# USB_UART_C.net
KiCad netlist of a schematic drawn in Altium Designer
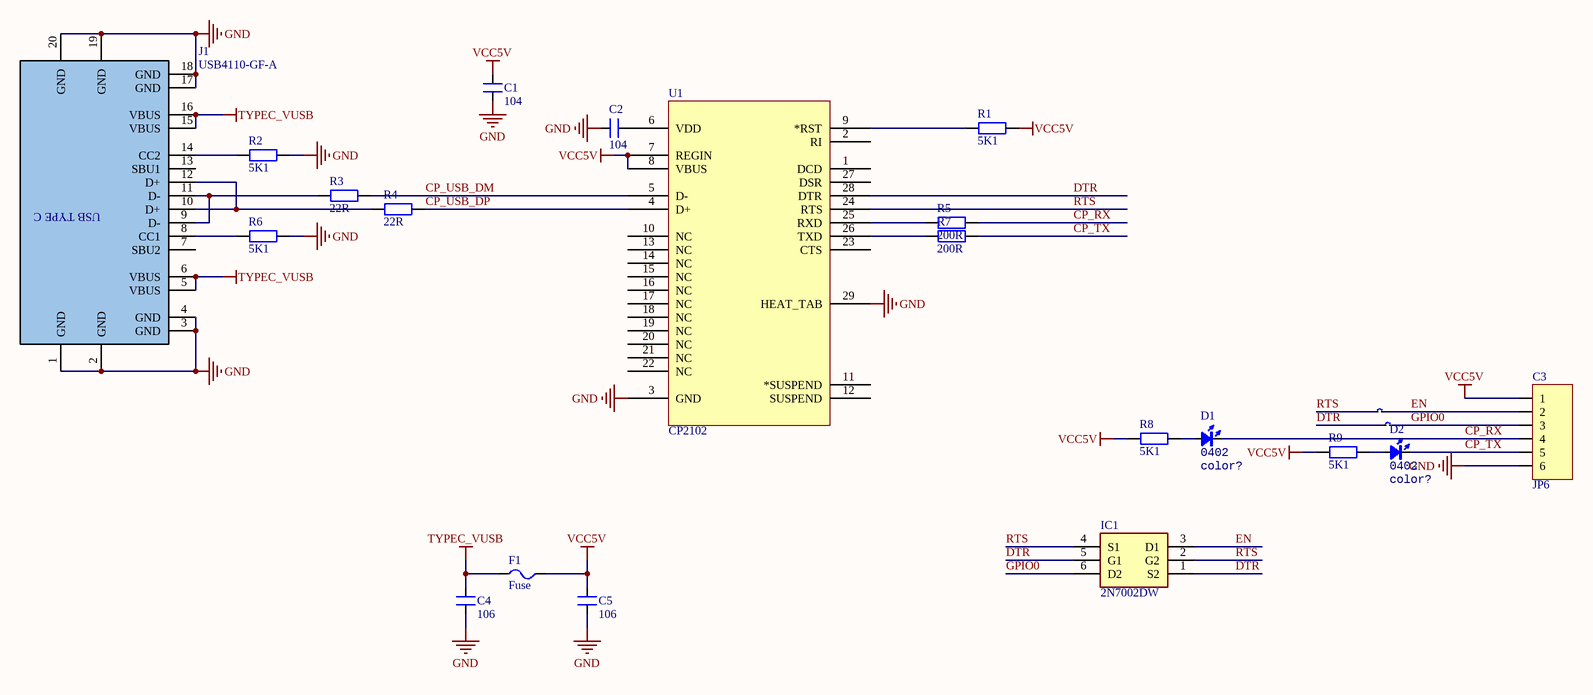
[diagram p0: USB_UART_C.SchDoc]

(export (version "E")
  (design (tool "Eeschema 10.0.6"))
  (components
    (comp (ref "C1")
      (value "104")
      (footprint "CAP_0402")
      (description "Cap SMD")
      (libsource (lib "OBIT_TESLA") (part "CM"))
    )
    (comp (ref "C2")
      (value "104")
      (footprint "CAP_0402")
      (description "Cap SMD")
      (libsource (lib "OBIT_TESLA") (part "CM"))
    )
    (comp (ref "C3")
      (value "JP6")
      (footprint "JP6-C1T")
      (description "WR-PHD 2.54 mm Angled Socket Header")
      (fields
        (field (name "MANUFACTURER") "Würth Elektronik eiSos GmbH")
        (field (name "PARTNO") "613006143121")
        (field (name "CREATED BY") "Karrer Zheng")
      )
      (libsource (lib "OBIT_TESLA") (part "JP6"))
    )
    (comp (ref "C4")
      (value "106")
      (footprint "CAP_0402")
      (description "Cap SMD")
      (libsource (lib "OBIT_TESLA") (part "CM"))
    )
    (comp (ref "C5")
      (value "106")
      (footprint "CAP_0402")
      (description "Cap SMD")
      (libsource (lib "OBIT_TESLA") (part "CM"))
    )
    (comp (ref "D1")
      (value "color?")
      (footprint "LED_0402_RED")
      (description "LED")
      (fields (field (name "TYPE") "0402"))
      (libsource (lib "OBIT_TESLA") (part "LED_0402"))
    )
    (comp (ref "D2")
      (value "color?")
      (footprint "LED_0402_RED")
      (description "LED")
      (fields (field (name "TYPE") "0402"))
      (libsource (lib "OBIT_TESLA") (part "LED_0402"))
    )
    (comp (ref "F1") (value "Fuse") (footprint "RES-SMD-1812") (libsource (lib "OBIT_TESLA") (part "FUSE")))
    (comp (ref "IC1")
      (value "2N7002DW")
      (footprint "SOT65P210X110-6N")
      (description "Integrated Circuit")
      (fields (field (name "MOUSER PART NUMBER") "512-2N7002DW"))
      (libsource (lib "OBIT_TESLA") (part "2N7002DW"))
    )
    (comp (ref "J1")
      (value "USB4110-GF-A")
      (footprint "USB4110GFA")
      (description "USB TYPE C")
      (libsource (lib "OBIT_TESLA") (part "USB4110-GF-A"))
    )
    (comp (ref "R1")
      (value "5K1")
      (footprint "RES_0402")
      (description "Resistor R1/4W")
      (libsource (lib "OBIT_TESLA") (part "R"))
    )
    (comp (ref "R2")
      (value "5K1")
      (footprint "RES_0402")
      (description "Resistor R1/4W")
      (libsource (lib "OBIT_TESLA") (part "R"))
    )
    (comp (ref "R3")
      (value "22R")
      (footprint "RES_0402")
      (description "Resistor R1/4W")
      (libsource (lib "OBIT_TESLA") (part "R"))
    )
    (comp (ref "R4")
      (value "22R")
      (footprint "RES_0402")
      (description "Resistor R1/4W")
      (libsource (lib "OBIT_TESLA") (part "R"))
    )
    (comp (ref "R5")
      (value "200R")
      (footprint "RES_0402")
      (description "Resistor R1/4W")
      (libsource (lib "OBIT_TESLA") (part "R"))
    )
    (comp (ref "R6")
      (value "5K1")
      (footprint "RES_0402")
      (description "Resistor R1/4W")
      (libsource (lib "OBIT_TESLA") (part "R"))
    )
    (comp (ref "R7")
      (value "200R")
      (footprint "RES_0402")
      (description "Resistor R1/4W")
      (libsource (lib "OBIT_TESLA") (part "R"))
    )
    (comp (ref "R8")
      (value "5K1")
      (footprint "RES_0402")
      (description "Resistor R1/4W")
      (libsource (lib "OBIT_TESLA") (part "R"))
    )
    (comp (ref "R9")
      (value "5K1")
      (footprint "RES_0402")
      (description "Resistor R1/4W")
      (libsource (lib "OBIT_TESLA") (part "R"))
    )
    (comp (ref "SB1") (value "SB") (footprint "SB_0603") (libsource (lib "OBIT_TESLA") (part "SB")))
    (comp (ref "SB2") (value "SB") (footprint "SB_0603") (libsource (lib "OBIT_TESLA") (part "SB")))
    (comp (ref "U1")
      (value "CP2102")
      (footprint "QFN-28")
      (description "USB to TTL")
      (libsource (lib "OBIT_TESLA") (part "CP2102"))
    )
  )
  (nets
    (net (code "1") (name "/CP_RX") (class "Default")
      (node (ref "C3") (pin "4") (pinfunction "4_4") (pintype "passive"))
      (node (ref "D1") (pin "2") (pinfunction "K_2") (pintype "passive"))
      (node (ref "R5") (pin "2") (pinfunction "2_2") (pintype "passive"))
    )
    (net (code "2") (name "/CP_TX") (class "Default")
      (node (ref "C3") (pin "5") (pinfunction "5_5") (pintype "passive"))
      (node (ref "D2") (pin "2") (pinfunction "K_2") (pintype "passive"))
      (node (ref "R7") (pin "2") (pinfunction "2_2") (pintype "passive"))
    )
    (net (code "3") (name "/CP_USB_DM") (class "Default")
      (node (ref "R3") (pin "2") (pinfunction "2_2") (pintype "passive"))
      (node (ref "U1") (pin "5") (pinfunction "D-_5") (pintype "passive"))
    )
    (net (code "4") (name "/CP_USB_DP") (class "Default")
      (node (ref "R4") (pin "2") (pinfunction "2_2") (pintype "passive"))
      (node (ref "U1") (pin "4") (pinfunction "D+_4") (pintype "passive"))
    )
    (net (code "5") (name "/DTR") (class "Default")
      (node (ref "IC1") (pin "1") (pinfunction "S2_1") (pintype "passive"))
      (node (ref "IC1") (pin "5") (pinfunction "G1_5") (pintype "passive"))
      (node (ref "SB2") (pin "1") (pintype "passive"))
      (node (ref "U1") (pin "28") (pinfunction "DTR_28") (pintype "passive"))
    )
    (net (code "6") (name "/EN") (class "Default")
      (node (ref "C3") (pin "2") (pinfunction "2_2") (pintype "passive"))
      (node (ref "IC1") (pin "3") (pinfunction "D1_3") (pintype "passive"))
      (node (ref "SB1") (pin "2") (pintype "passive"))
    )
    (net (code "7") (name "/GPIO0") (class "Default")
      (node (ref "C3") (pin "3") (pinfunction "3_3") (pintype "passive"))
      (node (ref "IC1") (pin "6") (pinfunction "D2_6") (pintype "passive"))
      (node (ref "SB2") (pin "2") (pintype "passive"))
    )
    (net (code "8") (name "/RTS") (class "Default")
      (node (ref "IC1") (pin "2") (pinfunction "G2_2") (pintype "passive"))
      (node (ref "IC1") (pin "4") (pinfunction "S1_4") (pintype "passive"))
      (node (ref "SB1") (pin "1") (pintype "passive"))
      (node (ref "U1") (pin "24") (pinfunction "RTS_24") (pintype "passive"))
    )
    (net (code "9") (name "GND") (class "Default")
      (node (ref "C1") (pin "2") (pinfunction "2_2") (pintype "passive"))
      (node (ref "C2") (pin "1") (pinfunction "1_1") (pintype "passive"))
      (node (ref "C3") (pin "6") (pinfunction "6_6") (pintype "passive"))
      (node (ref "C4") (pin "2") (pinfunction "2_2") (pintype "passive"))
      (node (ref "C5") (pin "2") (pinfunction "2_2") (pintype "passive"))
      (node (ref "J1") (pin "1") (pinfunction "GND_1") (pintype "passive"))
      (node (ref "J1") (pin "17") (pinfunction "GND_17") (pintype "passive"))
      (node (ref "J1") (pin "18") (pinfunction "GND_18") (pintype "passive"))
      (node (ref "J1") (pin "19") (pinfunction "GND_19") (pintype "passive"))
      (node (ref "J1") (pin "2") (pinfunction "GND_2") (pintype "passive"))
      (node (ref "J1") (pin "20") (pinfunction "GND_20") (pintype "passive"))
      (node (ref "J1") (pin "3") (pinfunction "GND_3") (pintype "passive"))
      (node (ref "J1") (pin "4") (pinfunction "GND_4") (pintype "passive"))
      (node (ref "R2") (pin "2") (pinfunction "2_2") (pintype "passive"))
      (node (ref "R6") (pin "2") (pinfunction "2_2") (pintype "passive"))
      (node (ref "U1") (pin "29") (pinfunction "HEAT_TAB_29") (pintype "passive"))
      (node (ref "U1") (pin "3") (pinfunction "GND_3") (pintype "passive"))
    )
    (net (code "10") (name "Net-(D1-A)") (class "Default")
      (node (ref "D1") (pin "1") (pinfunction "A_1") (pintype "passive"))
      (node (ref "R8") (pin "1") (pinfunction "1_1") (pintype "passive"))
    )
    (net (code "11") (name "Net-(D2-A)") (class "Default")
      (node (ref "D2") (pin "1") (pinfunction "A_1") (pintype "passive"))
      (node (ref "R9") (pin "1") (pinfunction "1_1") (pintype "passive"))
    )
    (net (code "12") (name "Net-(J1-CC1)") (class "Default")
      (node (ref "J1") (pin "8") (pinfunction "CC1_8") (pintype "passive"))
      (node (ref "R6") (pin "1") (pinfunction "1_1") (pintype "passive"))
    )
    (net (code "13") (name "Net-(J1-CC2)") (class "Default")
      (node (ref "J1") (pin "14") (pinfunction "CC2_14") (pintype "passive"))
      (node (ref "R2") (pin "1") (pinfunction "1_1") (pintype "passive"))
    )
    (net (code "14") (name "Net-(J1-D+-Pad10)") (class "Default")
      (node (ref "J1") (pin "10") (pinfunction "D+_10") (pintype "passive"))
      (node (ref "J1") (pin "12") (pinfunction "D+_12") (pintype "passive"))
      (node (ref "R4") (pin "1") (pinfunction "1_1") (pintype "passive"))
    )
    (net (code "15") (name "Net-(J1-D--Pad11)") (class "Default")
      (node (ref "J1") (pin "11") (pinfunction "D-_11") (pintype "passive"))
      (node (ref "J1") (pin "9") (pinfunction "D-_9") (pintype "passive"))
      (node (ref "R3") (pin "1") (pinfunction "1_1") (pintype "passive"))
    )
    (net (code "16") (name "Net-(U1-*RST)") (class "Default")
      (node (ref "R1") (pin "1") (pinfunction "1_1") (pintype "passive"))
      (node (ref "U1") (pin "9") (pinfunction "*RST_9") (pintype "passive"))
    )
    (net (code "17") (name "Net-(U1-RXD)") (class "Default")
      (node (ref "R5") (pin "1") (pinfunction "1_1") (pintype "passive"))
      (node (ref "U1") (pin "25") (pinfunction "RXD_25") (pintype "passive"))
    )
    (net (code "18") (name "Net-(U1-TXD)") (class "Default")
      (node (ref "R7") (pin "1") (pinfunction "1_1") (pintype "passive"))
      (node (ref "U1") (pin "26") (pinfunction "TXD_26") (pintype "passive"))
    )
    (net (code "19") (name "Net-(U1-VDD)") (class "Default")
      (node (ref "C2") (pin "2") (pinfunction "2_2") (pintype "passive"))
      (node (ref "U1") (pin "6") (pinfunction "VDD_6") (pintype "passive"))
    )
    (net (code "20") (name "TYPEC_VUSB") (class "Default")
      (node (ref "C4") (pin "1") (pinfunction "1_1") (pintype "passive"))
      (node (ref "F1") (pin "1") (pinfunction "1_1") (pintype "passive"))
      (node (ref "J1") (pin "15") (pinfunction "VBUS_15") (pintype "passive"))
      (node (ref "J1") (pin "16") (pinfunction "VBUS_16") (pintype "passive"))
      (node (ref "J1") (pin "5") (pinfunction "VBUS_5") (pintype "passive"))
      (node (ref "J1") (pin "6") (pinfunction "VBUS_6") (pintype "passive"))
    )
    (net (code "21") (name "VCC5V") (class "Default")
      (node (ref "C1") (pin "1") (pinfunction "1_1") (pintype "passive"))
      (node (ref "C3") (pin "1") (pinfunction "1_1") (pintype "passive"))
      (node (ref "C5") (pin "1") (pinfunction "1_1") (pintype "passive"))
      (node (ref "F1") (pin "2") (pinfunction "2_2") (pintype "passive"))
      (node (ref "R1") (pin "2") (pinfunction "2_2") (pintype "passive"))
      (node (ref "R8") (pin "2") (pinfunction "2_2") (pintype "passive"))
      (node (ref "R9") (pin "2") (pinfunction "2_2") (pintype "passive"))
      (node (ref "U1") (pin "7") (pinfunction "REGIN_7") (pintype "passive"))
      (node (ref "U1") (pin "8") (pinfunction "VBUS_8") (pintype "passive"))
    )
    (net (code "22") (name "unconnected-(J1-SBU1-Pad13)") (class "Default")
      (node (ref "J1") (pin "13") (pinfunction "SBU1_13") (pintype "passive"))
    )
    (net (code "23") (name "unconnected-(J1-SBU2-Pad7)") (class "Default")
      (node (ref "J1") (pin "7") (pinfunction "SBU2_7") (pintype "passive"))
    )
    (net (code "24") (name "unconnected-(U1-*SUSPEND-Pad11)") (class "Default")
      (node (ref "U1") (pin "11") (pinfunction "*SUSPEND_11") (pintype "passive"))
    )
    (net (code "25") (name "unconnected-(U1-CTS-Pad23)") (class "Default")
      (node (ref "U1") (pin "23") (pinfunction "CTS_23") (pintype "passive"))
    )
    (net (code "26") (name "unconnected-(U1-DCD-Pad1)") (class "Default")
      (node (ref "U1") (pin "1") (pinfunction "DCD_1") (pintype "passive"))
    )
    (net (code "27") (name "unconnected-(U1-DSR-Pad27)") (class "Default")
      (node (ref "U1") (pin "27") (pinfunction "DSR_27") (pintype "passive"))
    )
    (net (code "28") (name "unconnected-(U1-NC-Pad10)") (class "Default")
      (node (ref "U1") (pin "10") (pinfunction "NC_10") (pintype "passive"))
    )
    (net (code "29") (name "unconnected-(U1-NC-Pad13)") (class "Default")
      (node (ref "U1") (pin "13") (pinfunction "NC_13") (pintype "passive"))
    )
    (net (code "30") (name "unconnected-(U1-NC-Pad14)") (class "Default")
      (node (ref "U1") (pin "14") (pinfunction "NC_14") (pintype "passive"))
    )
    (net (code "31") (name "unconnected-(U1-NC-Pad15)") (class "Default")
      (node (ref "U1") (pin "15") (pinfunction "NC_15") (pintype "passive"))
    )
    (net (code "32") (name "unconnected-(U1-NC-Pad16)") (class "Default")
      (node (ref "U1") (pin "16") (pinfunction "NC_16") (pintype "passive"))
    )
    (net (code "33") (name "unconnected-(U1-NC-Pad17)") (class "Default")
      (node (ref "U1") (pin "17") (pinfunction "NC_17") (pintype "passive"))
    )
    (net (code "34") (name "unconnected-(U1-NC-Pad18)") (class "Default")
      (node (ref "U1") (pin "18") (pinfunction "NC_18") (pintype "passive"))
    )
    (net (code "35") (name "unconnected-(U1-NC-Pad19)") (class "Default")
      (node (ref "U1") (pin "19") (pinfunction "NC_19") (pintype "passive"))
    )
    (net (code "36") (name "unconnected-(U1-NC-Pad20)") (class "Default")
      (node (ref "U1") (pin "20") (pinfunction "NC_20") (pintype "passive"))
    )
    (net (code "37") (name "unconnected-(U1-NC-Pad21)") (class "Default")
      (node (ref "U1") (pin "21") (pinfunction "NC_21") (pintype "passive"))
    )
    (net (code "38") (name "unconnected-(U1-NC-Pad22)") (class "Default")
      (node (ref "U1") (pin "22") (pinfunction "NC_22") (pintype "passive"))
    )
    (net (code "39") (name "unconnected-(U1-RI-Pad2)") (class "Default")
      (node (ref "U1") (pin "2") (pinfunction "RI_2") (pintype "passive"))
    )
    (net (code "40") (name "unconnected-(U1-SUSPEND-Pad12)") (class "Default")
      (node (ref "U1") (pin "12") (pinfunction "SUSPEND_12") (pintype "passive"))
    )
  )
)
